# ProPrj_ESP32S3R8N8_CAN_Board_2026-01-26.net
KiCad netlist of a schematic drawn in EasyEDA Pro
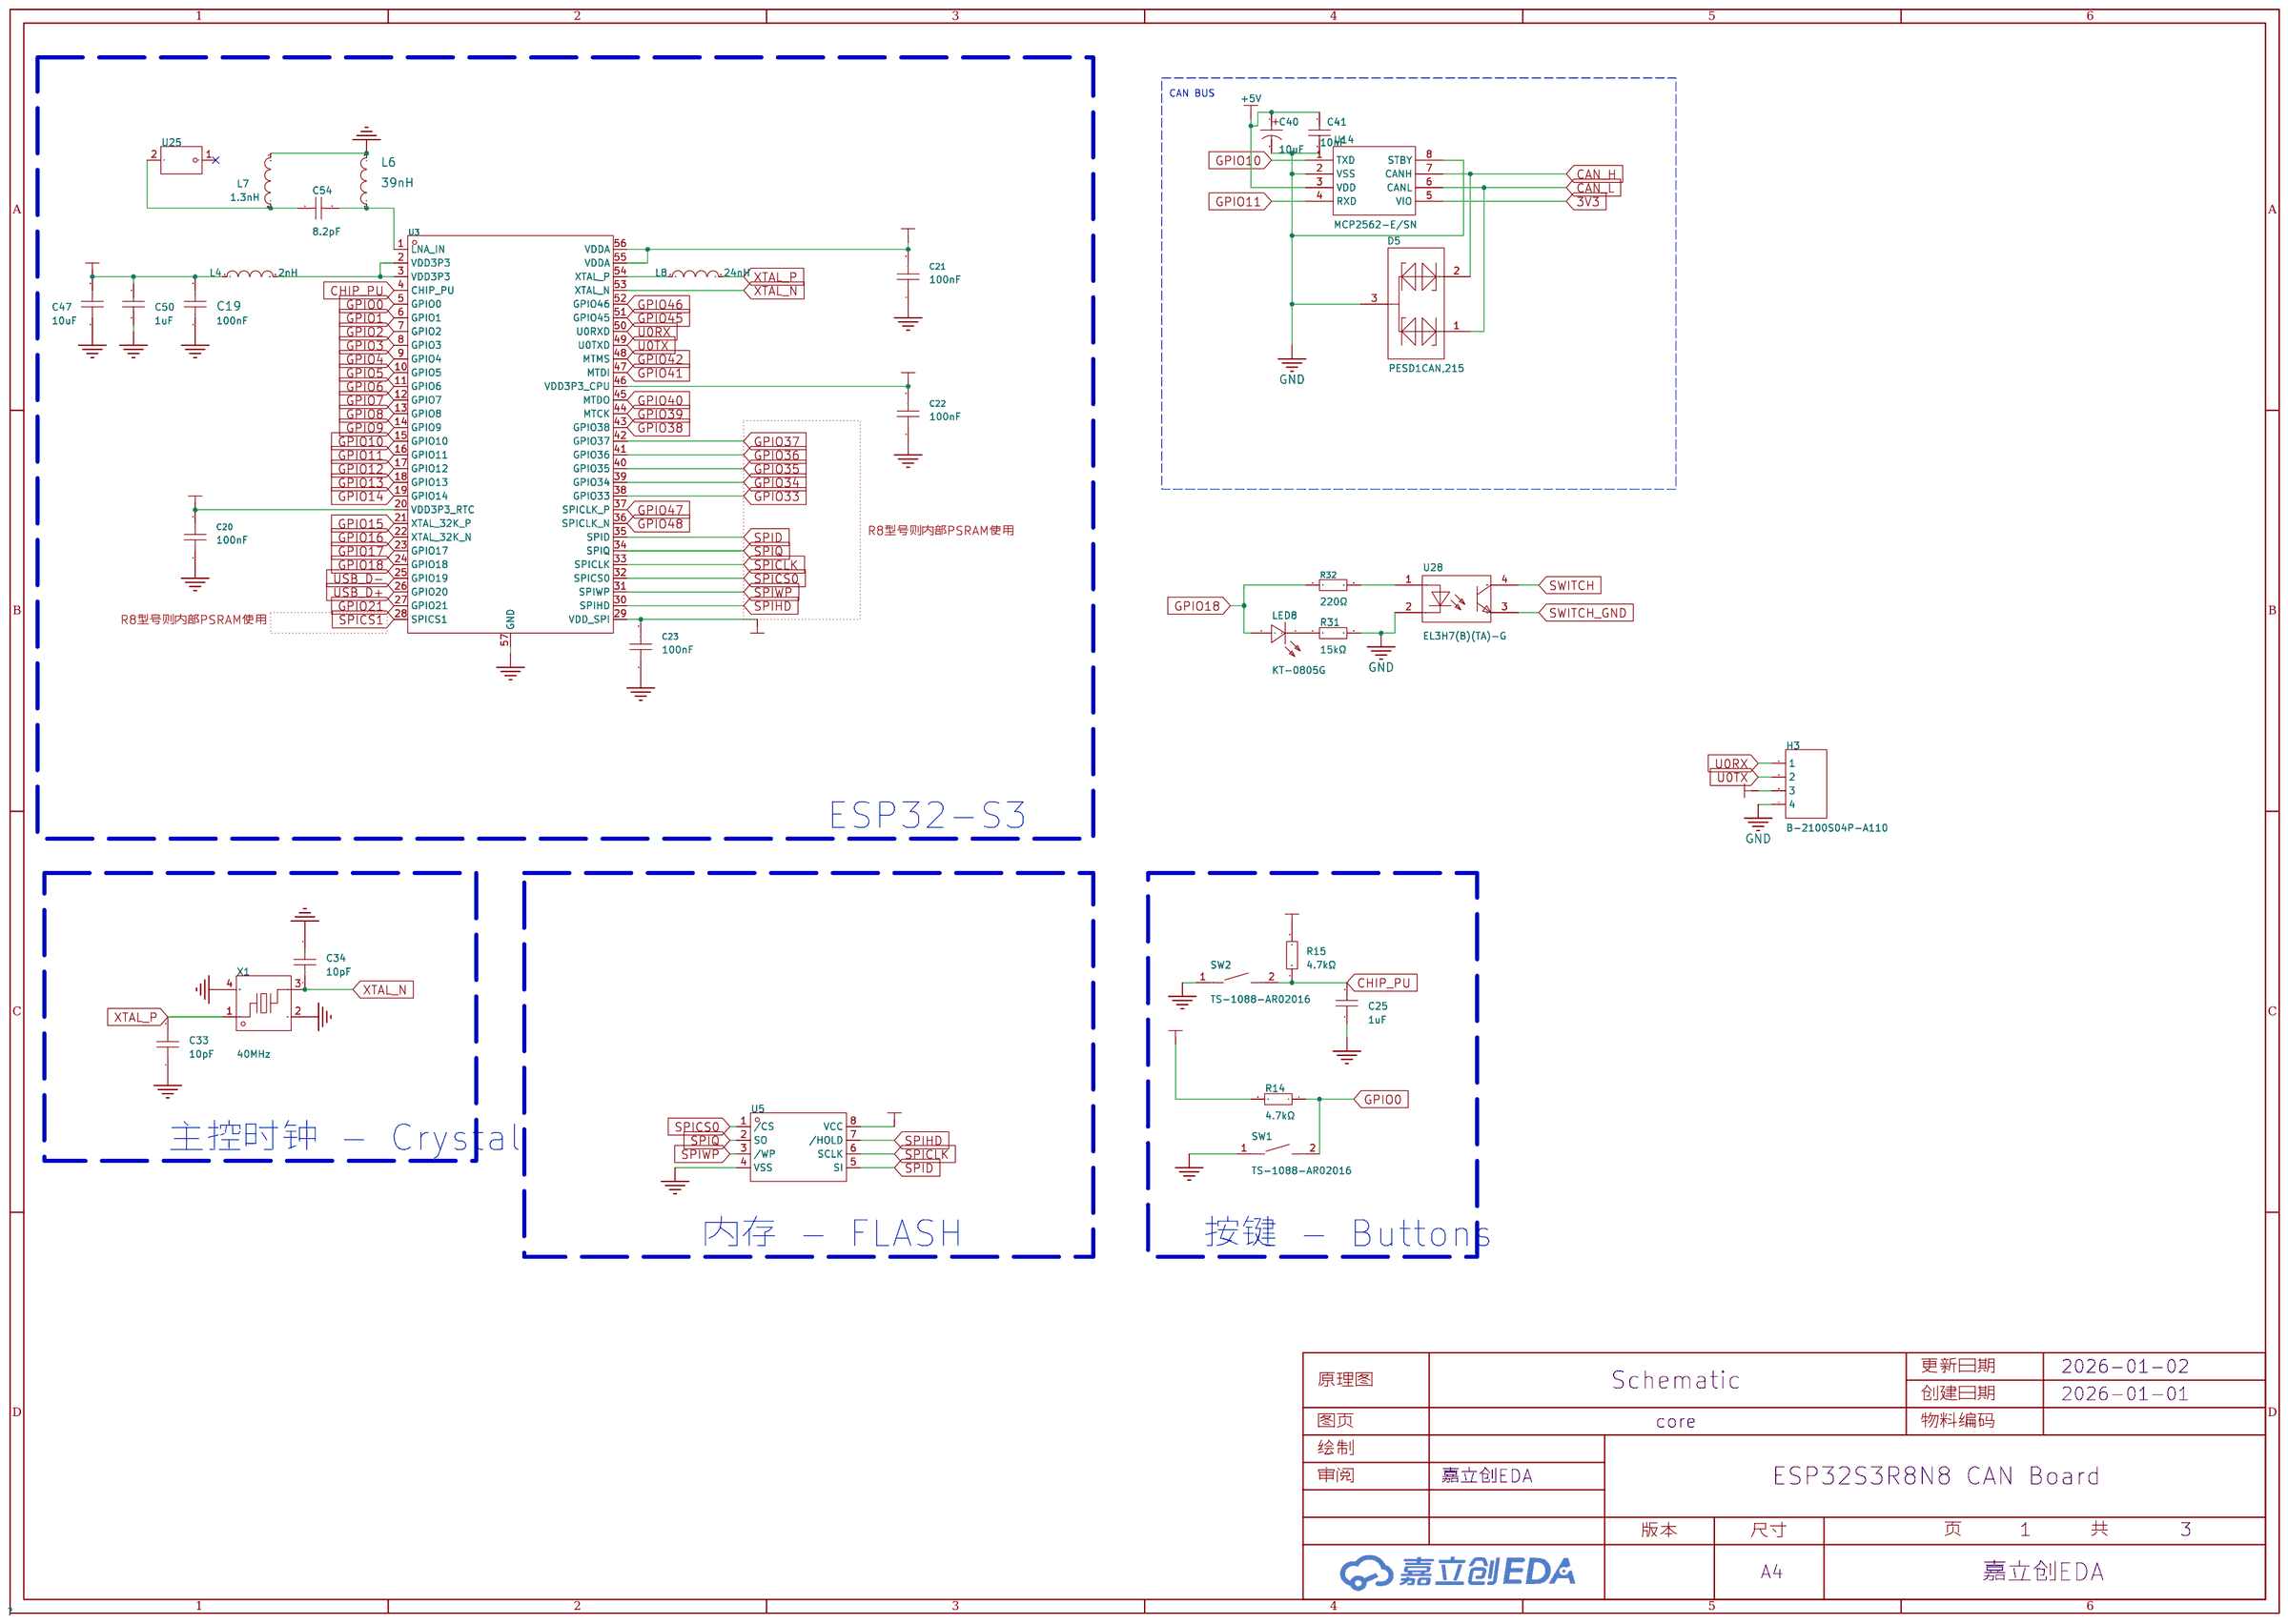
[diagram p0: core]
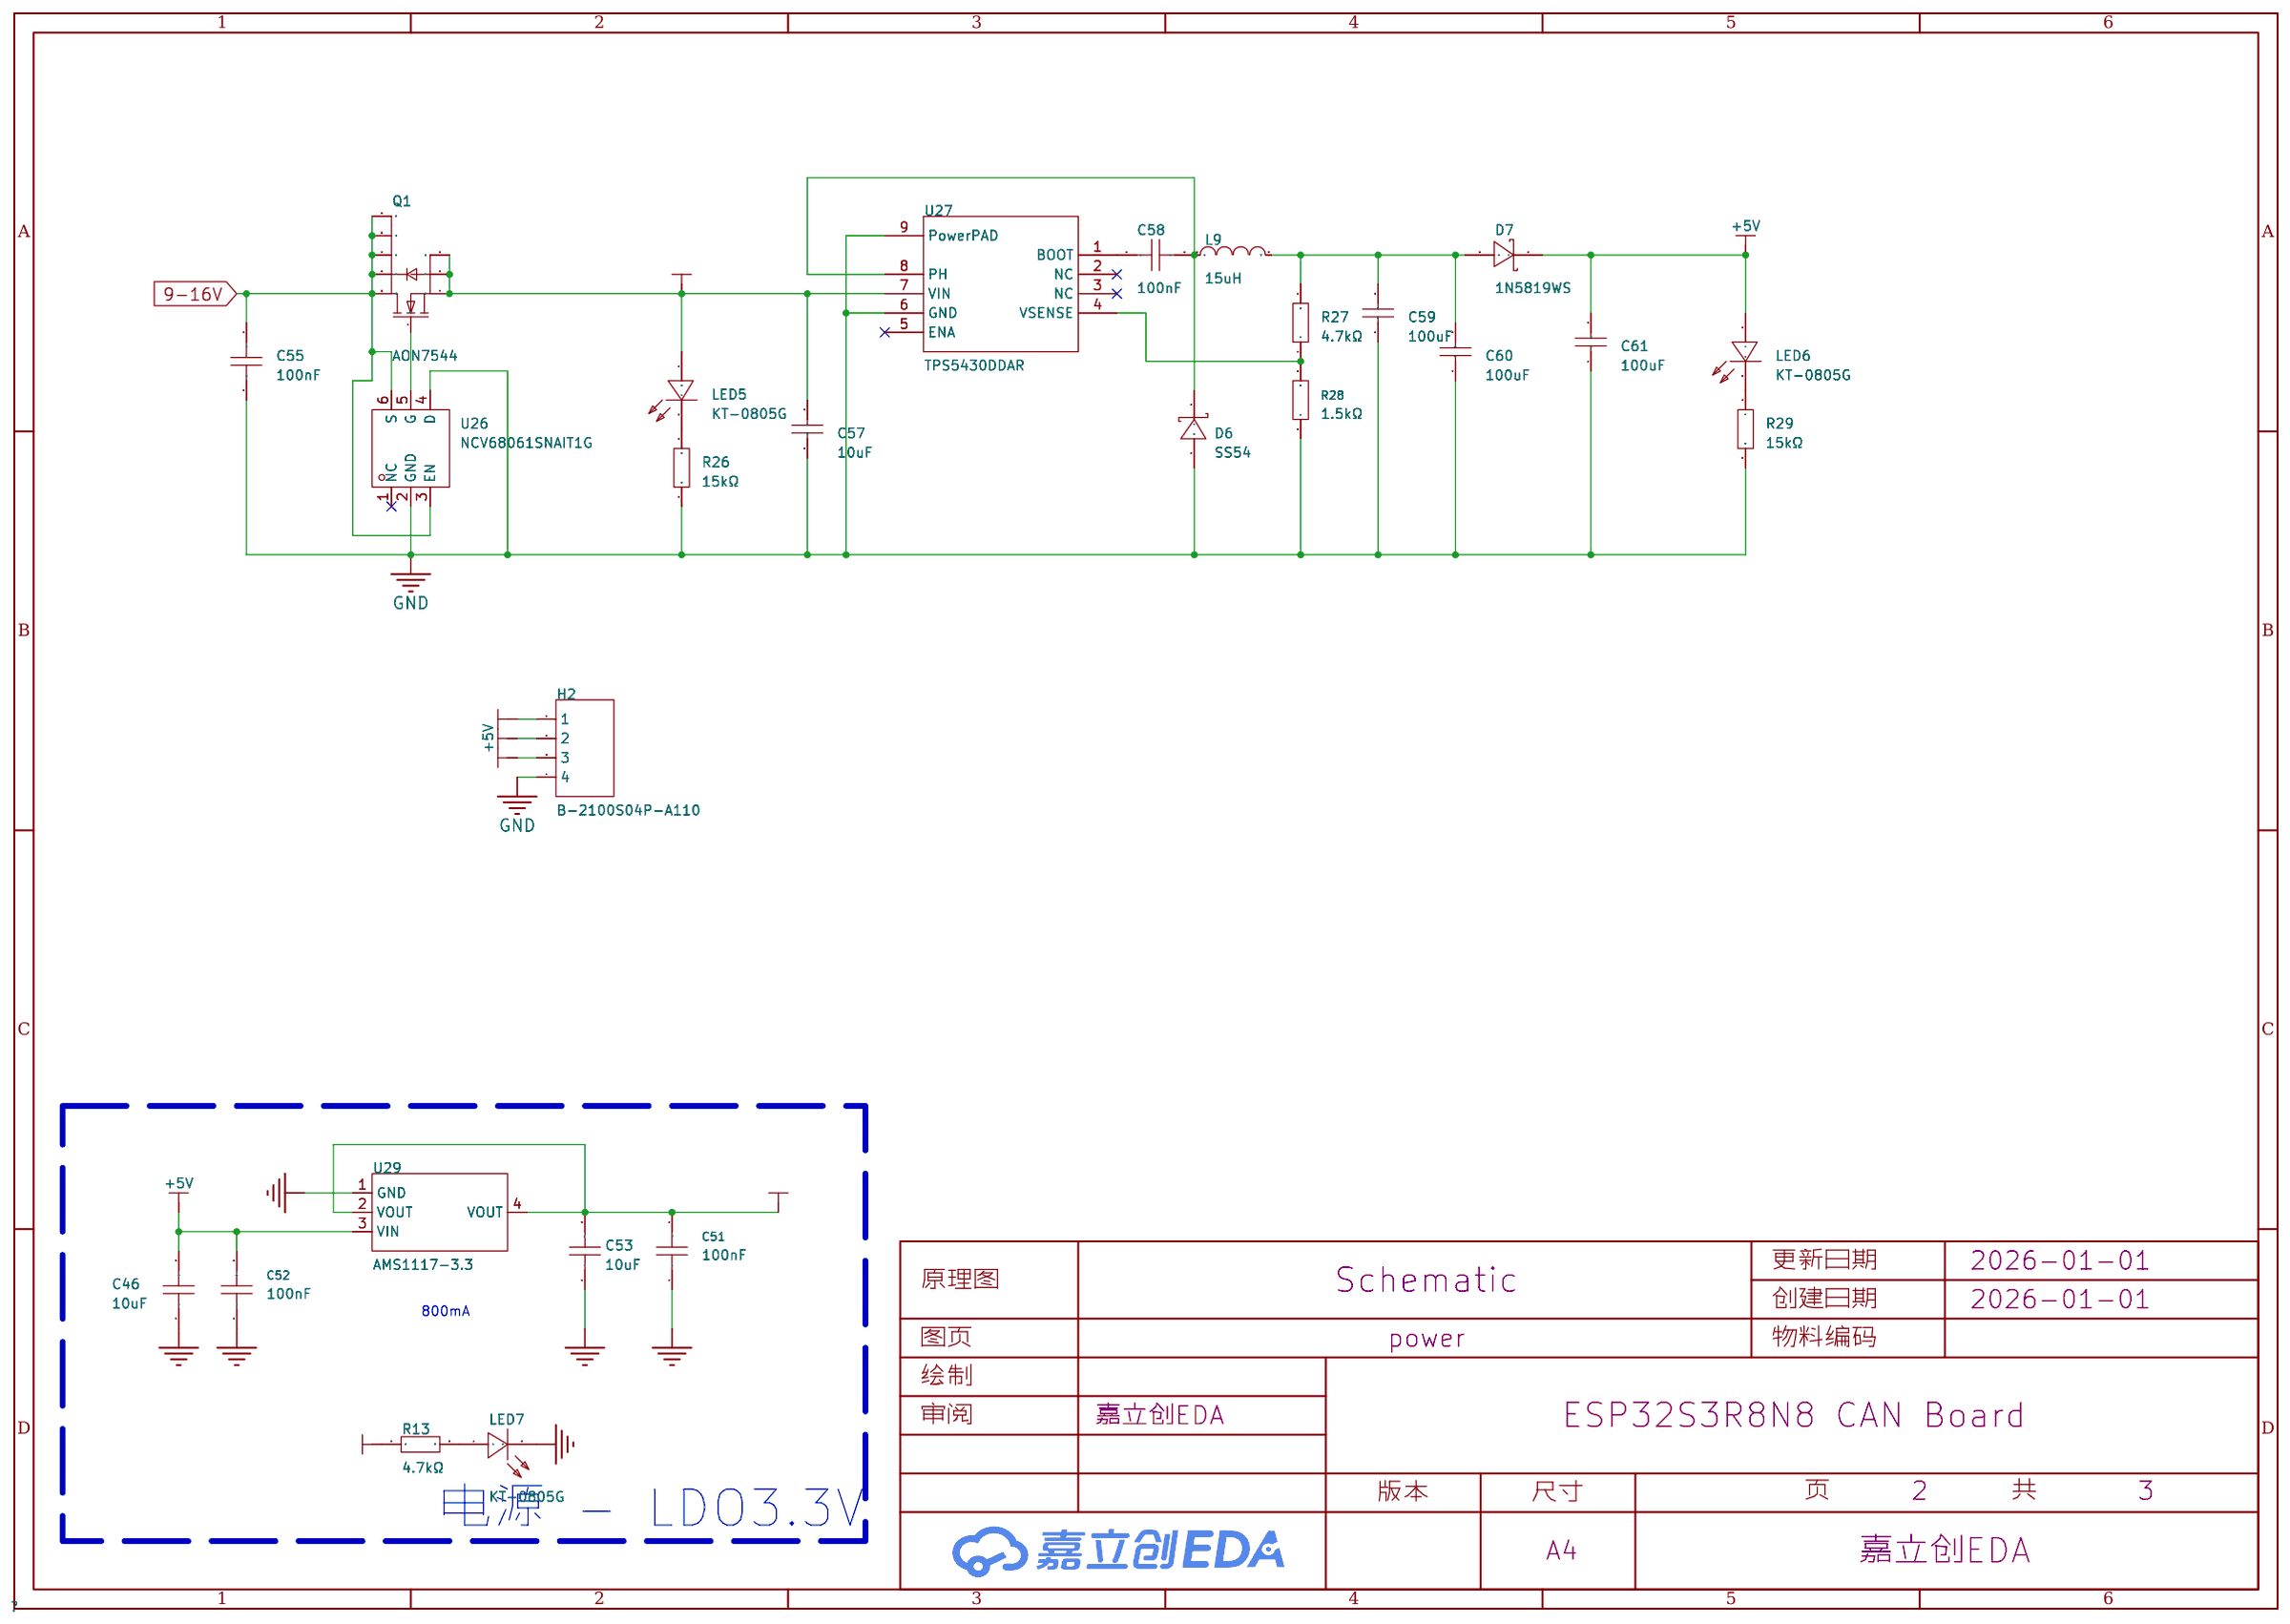
[diagram p1: power]
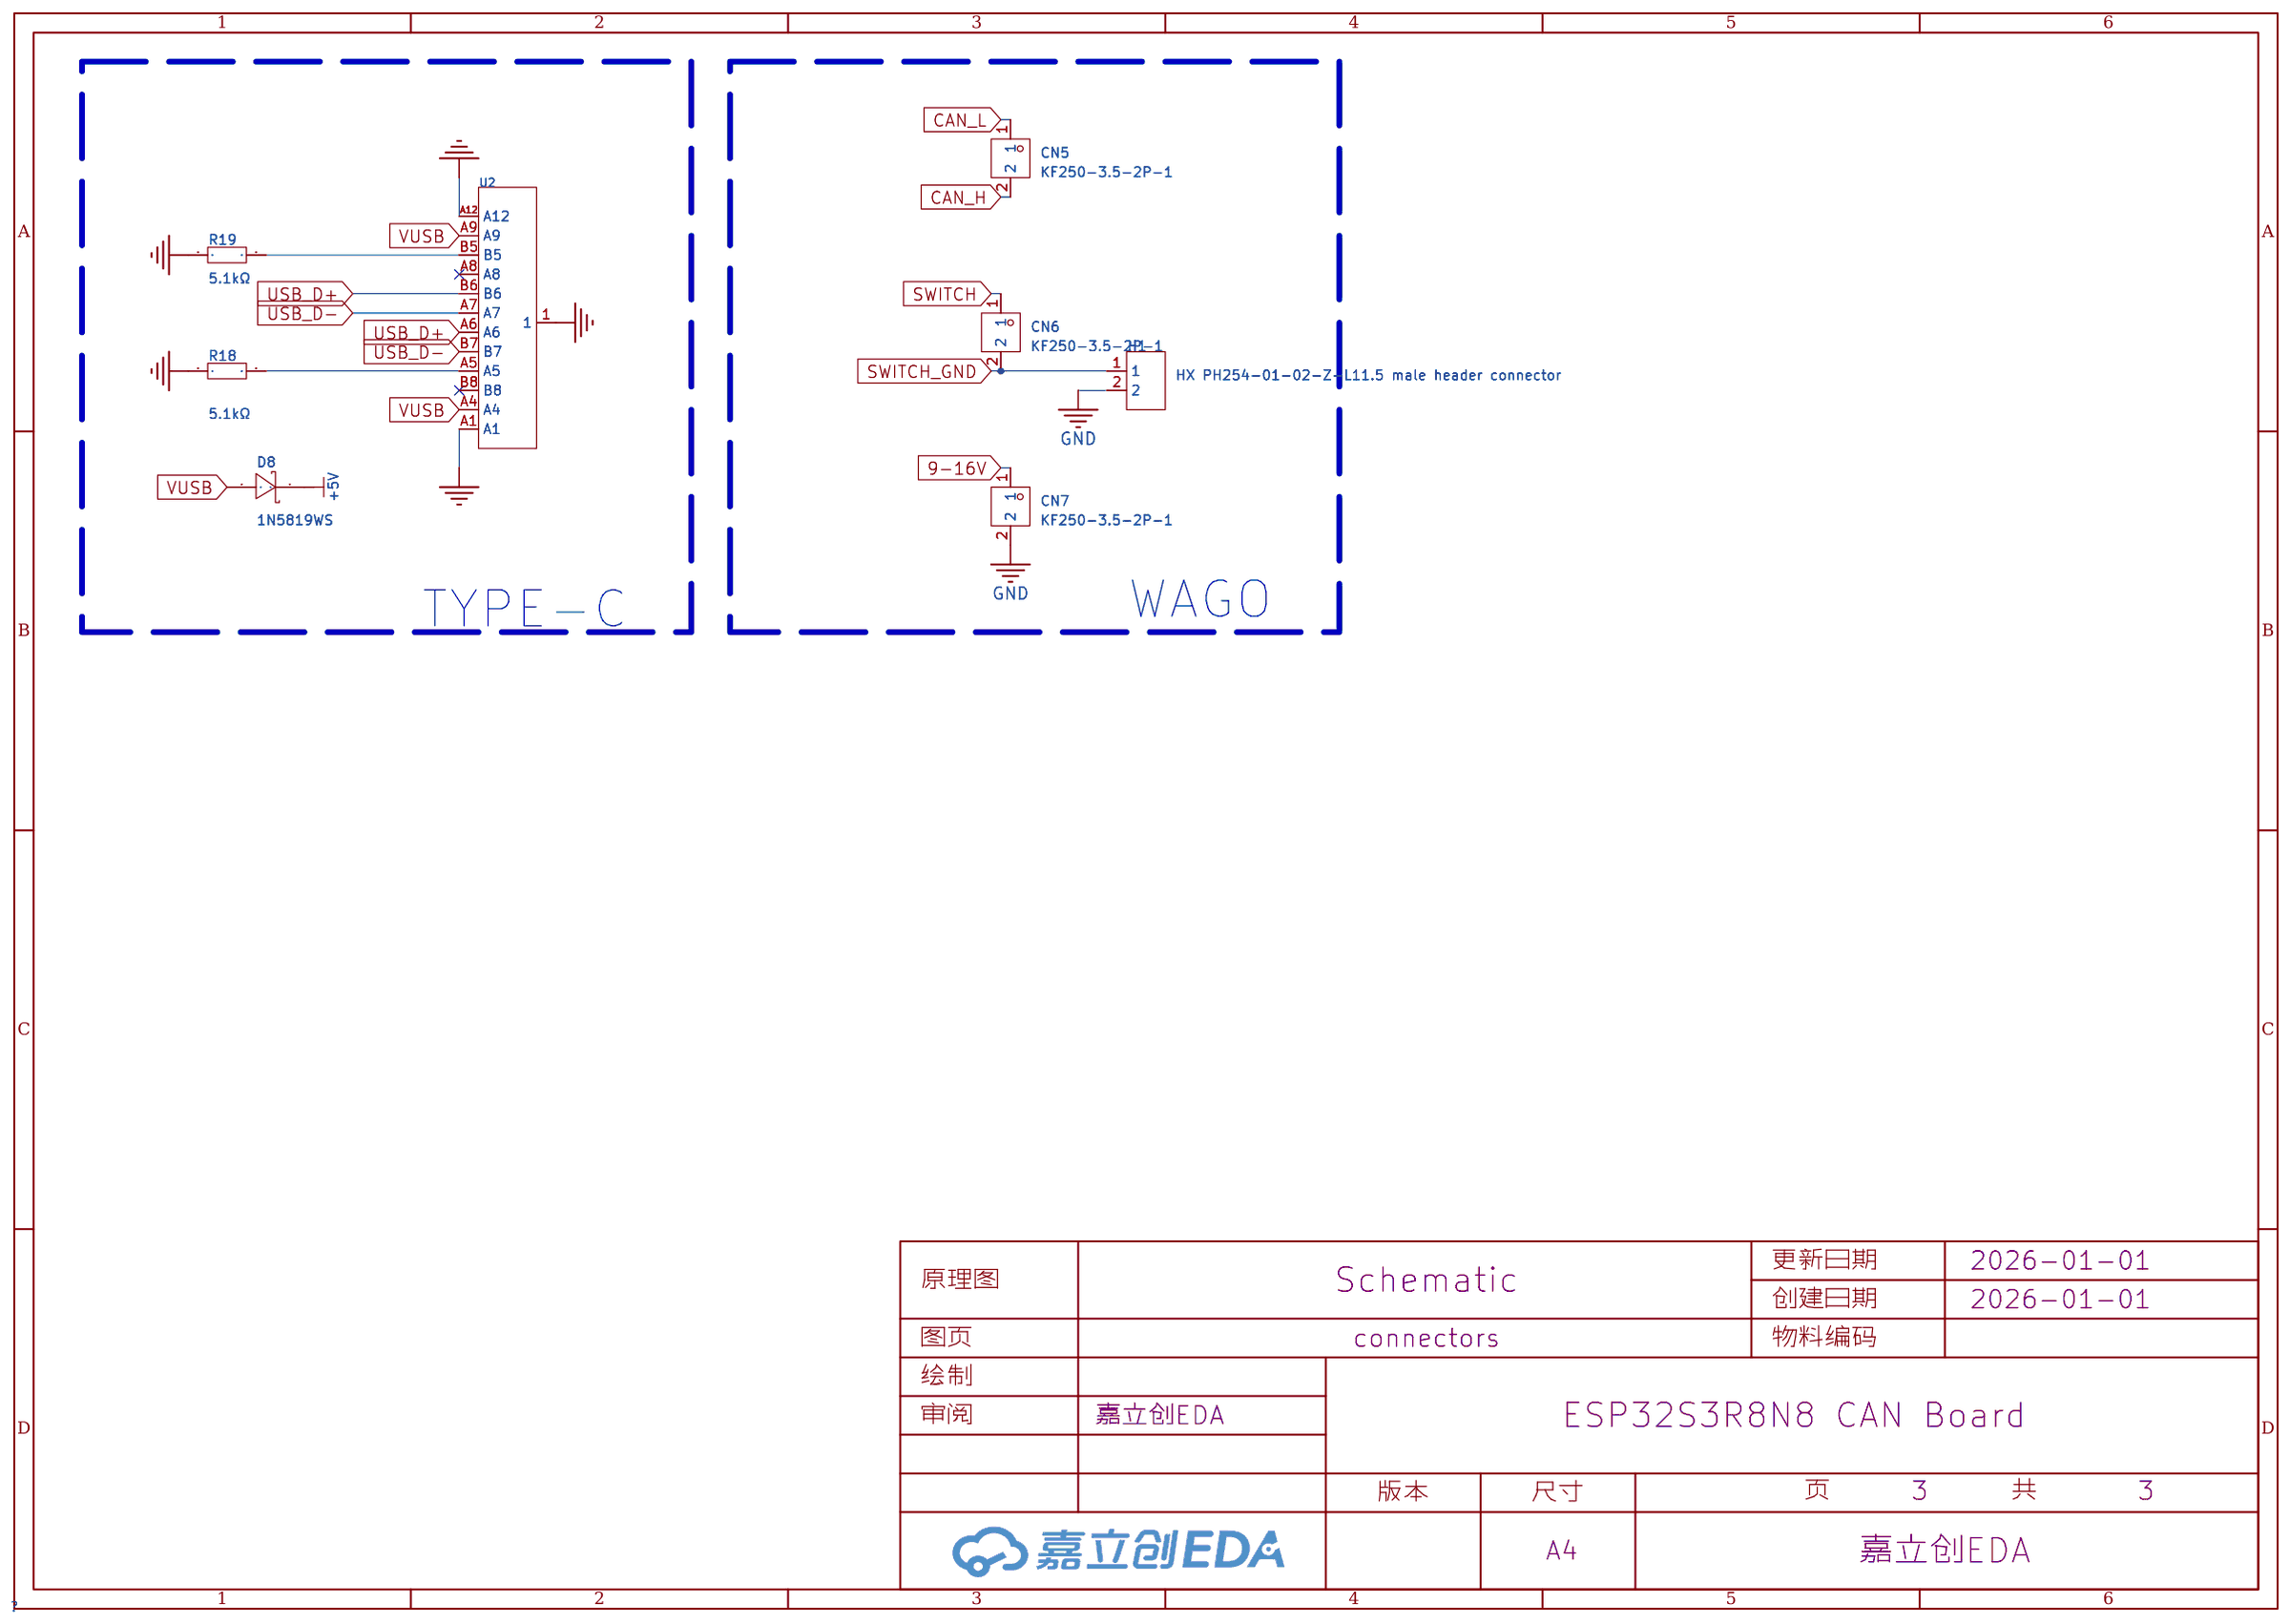
[diagram p2: connectors]

(export (version "E")
  (design (tool "Eeschema 10.0.6"))
  (components
    (comp (ref "C19")
      (value "100nF")
      (footprint "easyedapro:C0402")
      (description "容值:100nF;精度:±10%;额定电压:50V;材质(温度系数):X7R;")
      (fields
        (field (name "Manufacturer Part") "GRM155R71H104KE14D")
        (field (name "Manufacturer") "muRata(村田)")
      )
      (libsource (lib "easyedapro") (part "GRM155R71H104KE14D"))
    )
    (comp (ref "C20")
      (value "100nF")
      (footprint "easyedapro:C0402")
      (description "容值:100nF;精度:±10%;额定电压:50V;材质(温度系数):X7R;")
      (fields
        (field (name "Manufacturer Part") "GRM155R71H104KE14D")
        (field (name "Manufacturer") "muRata(村田)")
      )
      (libsource (lib "easyedapro") (part "GRM155R71H104KE14D"))
    )
    (comp (ref "C21")
      (value "100nF")
      (footprint "easyedapro:C0402")
      (description "容值:100nF;精度:±10%;额定电压:50V;材质(温度系数):X7R;")
      (fields
        (field (name "Manufacturer Part") "GRM155R71H104KE14D")
        (field (name "Manufacturer") "muRata(村田)")
      )
      (libsource (lib "easyedapro") (part "GRM155R71H104KE14D"))
    )
    (comp (ref "C22")
      (value "100nF")
      (footprint "easyedapro:C0402")
      (description "容值:100nF;精度:±10%;额定电压:50V;材质(温度系数):X7R;")
      (fields
        (field (name "Manufacturer Part") "GRM155R71H104KE14D")
        (field (name "Manufacturer") "muRata(村田)")
      )
      (libsource (lib "easyedapro") (part "GRM155R71H104KE14D"))
    )
    (comp (ref "C23")
      (value "100nF")
      (footprint "easyedapro:C0402")
      (description "容值:100nF;精度:±10%;额定电压:50V;材质(温度系数):X7R;")
      (fields
        (field (name "Manufacturer Part") "GRM155R71H104KE14D")
        (field (name "Manufacturer") "muRata(村田)")
      )
      (libsource (lib "easyedapro") (part "GRM155R71H104KE14D"))
    )
    (comp (ref "C25")
      (value "1uF")
      (footprint "easyedapro:C0402")
      (description "容值:1uF;精度:±10%;额定电压:10V;材质(温度系数):X5R;")
      (fields
        (field (name "Manufacturer Part") "CL05A105KP5NNNC")
        (field (name "Manufacturer") "SAMSUNG(三星)")
      )
      (libsource (lib "easyedapro") (part "CL05A105KP5NNNC"))
    )
    (comp (ref "C33")
      (value "10pF")
      (footprint "easyedapro:C0402")
      (description "容值:10pF;精度:±5%;额定电压:50V;材质(温度系数):C0G;")
      (fields
        (field (name "Manufacturer Part") "CL05C100JB5NNNC")
        (field (name "Manufacturer") "SAMSUNG(三星)")
      )
      (libsource (lib "easyedapro") (part "CL05C100JB5NNNC"))
    )
    (comp (ref "C34")
      (value "10pF")
      (footprint "easyedapro:C0402")
      (description "容值:10pF;精度:±5%;额定电压:50V;材质(温度系数):C0G;")
      (fields
        (field (name "Manufacturer Part") "CL05C100JB5NNNC")
        (field (name "Manufacturer") "SAMSUNG(三星)")
      )
      (libsource (lib "easyedapro") (part "CL05C100JB5NNNC"))
    )
    (comp (ref "C40")
      (value "10uF")
      (description "Capacitance:10uF Tolerance:±10% Tolerance:±10% Voltage Rating:50V Temperature Coefficient:X5R")
      (fields
        (field (name "Manufacturer Part") "CL31A106KBHNNNE")
        (field (name "Manufacturer") "SAMSUNG(三星)")
      )
      (libsource (lib "easyedapro") (part "CS1E100M-CRC54"))
    )
    (comp (ref "C41")
      (value "10nF")
      (footprint "easyedapro:C0402")
      (fields (field (name "Manufacturer Part") "CGA2B2X7R1E103KT0Y0F") (field (name "Manufacturer") "TDK"))
      (libsource (lib "easyedapro") (part "CGA2B2X7R1E103KT0Y0F"))
    )
    (comp (ref "C47")
      (value "10uF")
      (footprint "easyedapro:C0402")
      (description "Capacitance:10uF Tolerance:±10% Tolerance:±10% Voltage Rating:50V Temperature Coefficient:X5R")
      (fields
        (field (name "Manufacturer Part") "CL31A106KBHNNNE")
        (field (name "Manufacturer") "SAMSUNG(三星)")
      )
      (libsource (lib "easyedapro") (part "GRM155R61A106ME44D"))
    )
    (comp (ref "C50")
      (value "1uF")
      (footprint "easyedapro:C0402")
      (description "容值:1uF;精度:±10%;额定电压:10V;材质(温度系数):X5R;")
      (fields
        (field (name "Manufacturer Part") "CL05A105KP5NNNC")
        (field (name "Manufacturer") "SAMSUNG(三星)")
      )
      (libsource (lib "easyedapro") (part "CL05A105KP5NNNC"))
    )
    (comp (ref "C54")
      (value "8.2pF")
      (footprint "easyedapro:C0402")
      (description "容值:8.2pF;额定电压:50V;材质(温度系数):C0G;")
      (fields (field (name "Manufacturer Part") "0402CG8R2C500NT") (field (name "Manufacturer") "FH(风华)"))
      (libsource (lib "easyedapro") (part "0402CG8R2C500NT"))
    )
    (comp (ref "D5")
      (value "PESD1CAN,215")
      (footprint "easyedapro:SOT-23_L2.9-W1.3-P1.90-LS2.4-BR")
      (fields (field (name "Manufacturer") "Nexperia(安世)"))
      (libsource (lib "easyedapro") (part "PESD1CAN,215"))
    )
    (comp (ref "H3")
      (value "B-2100S04P-A110")
      (footprint "easyedapro:HDR-TH_4P-P2.54-V-M")
      (fields (field (name "Manufacturer") "Ckmtw(灿科盟)"))
      (libsource (lib "easyedapro") (part "Header-Male-2.54_1x4"))
    )
    (comp (ref "L4")
      (value "2nH")
      (footprint "easyedapro:L0402")
      (description "电感值:2nH;精度:-;额定电流:900mA;饱和电流(Isat):-;直流电阻(DCR):70mΩ;")
      (fields (field (name "Manufacturer Part") "MLG1005S2N0BT000") (field (name "Manufacturer") "TDK"))
      (libsource (lib "easyedapro") (part "MLG1005S2N0BT000"))
    )
    (comp (ref "L6")
      (value "39nH")
      (footprint "easyedapro:L0402")
      (description "电感值:39nH;额定电流:200mA;直流电阻(DCR):1Ω;精度:±5%;")
      (fields
        (field (name "Manufacturer Part") "SDCL1005C39NJTDF")
        (field (name "Manufacturer") "Sunlord(顺络)")
      )
      (libsource (lib "easyedapro") (part "SDCL1005C39NJTDF"))
    )
    (comp (ref "L7")
      (value "1.3nH")
      (footprint "easyedapro:L0402-RD")
      (description "电感值:1.3nH;精度:-;额定电流:400mA;直流电阻(DCR):100mΩ;饱和电流(Isat):-;")
      (fields
        (field (name "Manufacturer Part") "SDCL1005C1N3STDF")
        (field (name "Manufacturer") "Sunlord(顺络)")
      )
      (libsource (lib "easyedapro") (part "SDCL1005C1N3STDF"))
    )
    (comp (ref "L8")
      (value "24nH")
      (footprint "easyedapro:L0402-RD")
      (description "电感值:24nH;精度:±5%;额定电流:-;饱和电流(Isat):-;直流电阻(DCR):-;")
      (fields
        (field (name "Manufacturer Part") "SDCL1005C24NJTDF")
        (field (name "Manufacturer") "Sunlord(顺络)")
      )
      (libsource (lib "easyedapro") (part "SDCL1005C24NJTDF"))
    )
    (comp (ref "LED8")
      (value "KT-0805G")
      (footprint "easyedapro:LED0805-R-RD")
      (fields (field (name "Manufacturer") "KENTO"))
      (libsource (lib "easyedapro") (part "0805G (Green)"))
    )
    (comp (ref "R14")
      (value "4.7kΩ")
      (footprint "easyedapro:R0402")
      (fields
        (field (name "Manufacturer Part") "0402WGF4701TCE")
        (field (name "Manufacturer") "UNI-ROYAL(厚声)")
      )
      (libsource (lib "easyedapro") (part "0402WGJ0472TCE"))
    )
    (comp (ref "R15")
      (value "4.7kΩ")
      (footprint "easyedapro:R0402")
      (fields
        (field (name "Manufacturer Part") "0402WGF4701TCE")
        (field (name "Manufacturer") "UNI-ROYAL(厚声)")
      )
      (libsource (lib "easyedapro") (part "0402WGJ0472TCE"))
    )
    (comp (ref "R31")
      (value "15kΩ")
      (footprint "easyedapro:R0402")
      (description "电阻类型:厚膜电阻;阻值:15kΩ;精度:±1%;功率:62.5mW;")
      (fields
        (field (name "Manufacturer Part") "0402WGF1502TCE")
        (field (name "Manufacturer") "UNI-ROYAL(厚声)")
      )
      (libsource (lib "easyedapro") (part "0402WGF1502TCE"))
    )
    (comp (ref "R32")
      (value "220Ω")
      (footprint "easyedapro:R0402")
      (fields
        (field (name "Manufacturer Part") "0402WGF2200TCE")
        (field (name "Manufacturer") "UNI-ROYAL(厚声)")
      )
      (libsource (lib "easyedapro") (part "0402WGF2200TCE"))
    )
    (comp (ref "SW1")
      (value "TS-1088-AR02016")
      (footprint "easyedapro:SW-SMD_L3.9-W3.0-P4.45")
      (fields (field (name "Manufacturer") "XUNPU(讯普)"))
      (libsource (lib "easyedapro") (part "TS-1088-AR02016"))
    )
    (comp (ref "SW2")
      (value "TS-1088-AR02016")
      (footprint "easyedapro:SW-SMD_L3.9-W3.0-P4.45")
      (fields (field (name "Manufacturer") "XUNPU(讯普)"))
      (libsource (lib "easyedapro") (part "TS-1088-AR02016"))
    )
    (comp (ref "U3")
      (value "ESP32-S3(R8)")
      (footprint "easyedapro:QFN-56_L7.0-W7.0-P0.40-TL-EP4.0")
      (description "应用领域:蓝牙,WiFi;频率范围:2.412GHz~2.484GHz;数据速率:150Mbps;灵敏度:-98.4dBm;接口:I2C,I2S,SPI,UART,USB;")
      (fields (field (name "Manufacturer") "ESPRESSIF(乐鑫)"))
      (libsource (lib "easyedapro") (part "ESP32-S3(R8)"))
    )
    (comp (ref "U5")
      (value "BY25Q64ASSIG(T)")
      (footprint "easyedapro:SOIC-8_L5.3-W5.3-P1.27-LS8.0-BL")
      (fields (field (name "Manufacturer") "BOYAMICRO(博雅)"))
      (libsource (lib "easyedapro") (part "BY25Q64ASSIG(T)"))
    )
    (comp (ref "U14")
      (value "MCP2562-E/SN")
      (footprint "easyedapro:SOIC-8_L5.0-W4.0-P1.27-LS6.0-BL")
      (description "Type:Transceiver Supply Voltage:4.5V~5.5V Supply Voltage:4.5V~5.5V")
      (fields (field (name "Manufacturer") "MICROCHIP(美国微芯)"))
      (libsource (lib "easyedapro") (part "MCP2562-E/SN"))
    )
    (comp (ref "U25")
      (value "RFANT5220110A0T")
      (footprint "easyedapro:FILTER-SMD_L5.2-W2.0-L")
      (description "2.4 GHz 陶瓷天线")
      (fields (field (name "Manufacturer") "Walsin(华新科)"))
      (libsource (lib "easyedapro") (part "RFANT5220110A0T"))
    )
    (comp (ref "U28")
      (value "EL3H7(B)(TA)-G")
      (footprint "easyedapro:SSOP-4_L4.4-W2.7-P1.27-LS7.0-TL")
      (fields (field (name "Manufacturer") "EVERLIGHT(亿光)"))
      (libsource (lib "easyedapro") (part "EL3H7(B)(TA)-G_C5213653"))
    )
    (comp (ref "X1")
      (value "40MHz")
      (footprint "easyedapro:CRYSTAL-SMD_4P-L2.5-W2.0-BL")
      (description "频率:40MHz;频率公差:±10ppm;负载电容:10pF;")
      (fields (field (name "Manufacturer Part") "S2240000101050JY") (field (name "Manufacturer") "JGHC(晶光华)"))
      (libsource (lib "easyedapro") (part "S2240000101050JY"))
    )
    (comp (ref "C46")
      (value "10uF")
      (footprint "easyedapro:C0402")
      (description "Capacitance:10uF Tolerance:±10% Tolerance:±10% Voltage Rating:50V Temperature Coefficient:X5R")
      (fields
        (field (name "Manufacturer Part") "CL31A106KBHNNNE")
        (field (name "Manufacturer") "SAMSUNG(三星)")
      )
      (libsource (lib "easyedapro") (part "GRM155R61A106ME44D"))
    )
    (comp (ref "C51")
      (value "100nF")
      (footprint "easyedapro:C0402")
      (description "Capacitance:100nF Tolerance:±10% Tolerance:±10% Voltage Rating:50V Temperature Coefficient:X7R")
      (fields
        (field (name "Manufacturer Part") "CC0603KRX7R9BB104")
        (field (name "Manufacturer") "YAGEO(国巨)")
      )
      (libsource (lib "easyedapro") (part "GRM155R71H104KE14D"))
    )
    (comp (ref "C52")
      (value "100nF")
      (footprint "easyedapro:C0402")
      (description "Capacitance:100nF Tolerance:±10% Tolerance:±10% Voltage Rating:50V Temperature Coefficient:X7R")
      (fields
        (field (name "Manufacturer Part") "CC0603KRX7R9BB104")
        (field (name "Manufacturer") "YAGEO(国巨)")
      )
      (libsource (lib "easyedapro") (part "GRM155R71H104KE14D"))
    )
    (comp (ref "C53")
      (value "10uF")
      (footprint "easyedapro:C0402")
      (description "Capacitance:10uF Tolerance:±10% Tolerance:±10% Voltage Rating:50V Temperature Coefficient:X5R")
      (fields
        (field (name "Manufacturer Part") "CL31A106KBHNNNE")
        (field (name "Manufacturer") "SAMSUNG(三星)")
      )
      (libsource (lib "easyedapro") (part "GRM155R61A106ME44D"))
    )
    (comp (ref "C55")
      (value "100nF")
      (footprint "easyedapro:C0603")
      (description "Capacitance:100nF Tolerance:±10% Tolerance:±10% Voltage Rating:50V Temperature Coefficient:X7R")
      (fields
        (field (name "Manufacturer Part") "CC0603KRX7R9BB104")
        (field (name "Manufacturer") "YAGEO(国巨)")
      )
      (libsource (lib "easyedapro") (part "CC0603KRX7R9BB104"))
    )
    (comp (ref "C57")
      (value "10uF")
      (footprint "easyedapro:C1206")
      (description "Capacitance:10uF Tolerance:±10% Tolerance:±10% Voltage Rating:50V Temperature Coefficient:X5R")
      (fields
        (field (name "Manufacturer Part") "CL31A106KBHNNNE")
        (field (name "Manufacturer") "SAMSUNG(三星)")
      )
      (libsource (lib "easyedapro") (part "CL31A106KBHNNNE"))
    )
    (comp (ref "C58")
      (value "100nF")
      (footprint "easyedapro:C0603")
      (description "Capacitance:100nF Tolerance:±10% Tolerance:±10% Voltage Rating:50V Temperature Coefficient:X7R")
      (fields
        (field (name "Manufacturer Part") "CC0603KRX7R9BB104")
        (field (name "Manufacturer") "YAGEO(国巨)")
      )
      (libsource (lib "easyedapro") (part "CC0603KRX7R9BB104"))
    )
    (comp (ref "C59")
      (value "100uF")
      (footprint "easyedapro:C1206")
      (description "Capacitance:100uF Tolerance:±20% Tolerance:±20% Voltage Rating:6.3V Temperature Coefficient:X5R")
      (fields
        (field (name "Manufacturer Part") "CL31A107MQHNNNE")
        (field (name "Manufacturer") "SAMSUNG(三星)")
      )
      (libsource (lib "easyedapro") (part "CL31A107MQHNNNE"))
    )
    (comp (ref "C60")
      (value "100uF")
      (footprint "easyedapro:C1206")
      (description "Capacitance:100uF Tolerance:±20% Tolerance:±20% Voltage Rating:6.3V Temperature Coefficient:X5R")
      (fields
        (field (name "Manufacturer Part") "CL31A107MQHNNNE")
        (field (name "Manufacturer") "SAMSUNG(三星)")
      )
      (libsource (lib "easyedapro") (part "CL31A107MQHNNNE"))
    )
    (comp (ref "C61")
      (value "100uF")
      (footprint "easyedapro:C1206")
      (description "Capacitance:100uF Tolerance:±20% Tolerance:±20% Voltage Rating:6.3V Temperature Coefficient:X5R")
      (fields
        (field (name "Manufacturer Part") "CL31A107MQHNNNE")
        (field (name "Manufacturer") "SAMSUNG(三星)")
      )
      (libsource (lib "easyedapro") (part "CL31A107MQHNNNE"))
    )
    (comp (ref "D6")
      (value "SS54")
      (footprint "easyedapro:SMA_L4.4-W2.8-LS5.4-R-RD")
      (fields (field (name "Manufacturer") "MDD(辰达半导体)"))
      (libsource (lib "easyedapro") (part "SS54_C22452"))
    )
    (comp (ref "D7")
      (value "1N5819WS")
      (footprint "easyedapro:SOD-323_L1.8-W1.3-LS2.5-RD")
      (fields (field (name "Manufacturer") "Hottech(合科泰)"))
      (libsource (lib "easyedapro") (part "1N5819WS"))
    )
    (comp (ref "H2")
      (value "B-2100S04P-A110")
      (footprint "easyedapro:HDR-TH_4P-P2.54-V-M")
      (fields (field (name "Manufacturer") "Ckmtw(灿科盟)"))
      (libsource (lib "easyedapro") (part "Header-Male-2.54_1x4"))
    )
    (comp (ref "L9")
      (value "15uH")
      (footprint "easyedapro:IND-SMD_L7.0-W6.6_FXL0630")
      (fields (field (name "Manufacturer Part") "FXL0630-150-M") (field (name "Manufacturer") "cjiang(长江微电)"))
      (libsource (lib "easyedapro") (part "FXL0630-150-M"))
    )
    (comp (ref "LED5")
      (value "KT-0805G")
      (footprint "easyedapro:LED0805-R-RD")
      (fields (field (name "Manufacturer") "KENTO"))
      (libsource (lib "easyedapro") (part "0805G (Green)"))
    )
    (comp (ref "LED6")
      (value "KT-0805G")
      (footprint "easyedapro:LED0805-R-RD")
      (fields (field (name "Manufacturer") "KENTO"))
      (libsource (lib "easyedapro") (part "0805G (Green)"))
    )
    (comp (ref "LED7")
      (value "KT-0805G")
      (footprint "easyedapro:LED0805-R-RD")
      (fields (field (name "Manufacturer") "KENTO"))
      (libsource (lib "easyedapro") (part "0805G (Green)"))
    )
    (comp (ref "Q1")
      (value "AON7544")
      (footprint "easyedapro:DFN-8_L3.2-W3.1-P0.65-LS3.4-BL")
      (fields (field (name "Manufacturer") "HXY MOSFET(华轩阳电子)"))
      (libsource (lib "easyedapro") (part "AON7544_C5261066"))
    )
    (comp (ref "R13")
      (value "4.7kΩ")
      (footprint "easyedapro:R0402")
      (fields
        (field (name "Manufacturer Part") "0402WGF4701TCE")
        (field (name "Manufacturer") "UNI-ROYAL(厚声)")
      )
      (libsource (lib "easyedapro") (part "0402WGJ0472TCE"))
    )
    (comp (ref "R26")
      (value "15kΩ")
      (footprint "easyedapro:R0402")
      (description "电阻类型:厚膜电阻;阻值:15kΩ;精度:±1%;功率:62.5mW;")
      (fields
        (field (name "Manufacturer Part") "0402WGF1502TCE")
        (field (name "Manufacturer") "UNI-ROYAL(厚声)")
      )
      (libsource (lib "easyedapro") (part "0402WGF1502TCE"))
    )
    (comp (ref "R27")
      (value "4.7kΩ")
      (footprint "easyedapro:R0402")
      (fields
        (field (name "Manufacturer Part") "0402WGF4701TCE")
        (field (name "Manufacturer") "UNI-ROYAL(厚声)")
      )
      (libsource (lib "easyedapro") (part "0402WGJ0472TCE"))
    )
    (comp (ref "R28")
      (value "1.5kΩ")
      (footprint "easyedapro:R0402")
      (fields
        (field (name "Manufacturer Part") "0402WGF1501TCE")
        (field (name "Manufacturer") "UNI-ROYAL(厚声)")
      )
      (libsource (lib "easyedapro") (part "0402WGF1501TCE"))
    )
    (comp (ref "R29")
      (value "15kΩ")
      (footprint "easyedapro:R0402")
      (description "电阻类型:厚膜电阻;阻值:15kΩ;精度:±1%;功率:62.5mW;")
      (fields
        (field (name "Manufacturer Part") "0402WGF1502TCE")
        (field (name "Manufacturer") "UNI-ROYAL(厚声)")
      )
      (libsource (lib "easyedapro") (part "0402WGF1502TCE"))
    )
    (comp (ref "U26")
      (value "NCV68061SNAIT1G")
      (footprint "easyedapro:TSOP-6_L3.0-W1.5-P0.95-BL")
      (fields (field (name "Manufacturer") "onsemi(安森美)"))
      (libsource (lib "easyedapro") (part "NCV68061SNAIT1G"))
    )
    (comp (ref "U27")
      (value "TPS5430DDAR")
      (footprint "easyedapro:ESOP-8_L4.9-W3.9-P1.27-LS6.0-TL-EP")
      (fields (field (name "Manufacturer") "TI(德州仪器)"))
      (libsource (lib "easyedapro") (part "TPS5430DDAR"))
    )
    (comp (ref "U29")
      (value "AMS1117-3.3")
      (footprint "easyedapro:SOT-223-3_L6.5-W3.4-P2.30-LS7.0-BR")
      (fields (field (name "Manufacturer") "AMS"))
      (libsource (lib "easyedapro") (part "AMS1117-3.3"))
    )
    (comp (ref "CN5")
      (value "KF250-3.5-2P-1")
      (footprint "easyedapro:CONN-TH_P3.50_KF250-3.5-2P-1")
      (fields (field (name "Manufacturer") "KEFA(科发)"))
      (libsource (lib "easyedapro") (part "KF250-3.5-2P-1"))
    )
    (comp (ref "CN6")
      (value "KF250-3.5-2P-1")
      (footprint "easyedapro:CONN-TH_P3.50_KF250-3.5-2P-1")
      (fields (field (name "Manufacturer") "KEFA(科发)"))
      (libsource (lib "easyedapro") (part "KF250-3.5-2P-1"))
    )
    (comp (ref "CN7")
      (value "KF250-3.5-2P-1")
      (footprint "easyedapro:CONN-TH_P3.50_KF250-3.5-2P-1")
      (fields (field (name "Manufacturer") "KEFA(科发)"))
      (libsource (lib "easyedapro") (part "KF250-3.5-2P-1"))
    )
    (comp (ref "D8")
      (value "1N5819WS")
      (footprint "easyedapro:SOD-323_L1.8-W1.3-LS2.5-RD")
      (fields (field (name "Manufacturer") "Hottech(合科泰)"))
      (libsource (lib "easyedapro") (part "1N5819WS"))
    )
    (comp (ref "H1")
      (value "HX PH254-01-02-Z-L11.5 male header connector")
      (footprint "easyedapro:HDR-TH_2P-P2.54-V-M_C9900056156")
      (fields (field (name "Manufacturer") "hanxia(韩下)"))
      (libsource (lib "easyedapro") (part "HX PH254-01-02-Z-L11.5 MALE HEADER CONNECTOR"))
    )
    (comp (ref "R18")
      (value "5.1kΩ")
      (footprint "easyedapro:R0402")
      (description "电阻类型:厚膜电阻;阻值:5.1kΩ;精度:±1%;功率:62.5mW;")
      (fields
        (field (name "Manufacturer Part") "0402WGF5101TCE")
        (field (name "Manufacturer") "UNI-ROYAL(厚声)")
      )
      (libsource (lib "easyedapro") (part "0402WGF5101TCE"))
    )
    (comp (ref "R19")
      (value "5.1kΩ")
      (footprint "easyedapro:R0402")
      (description "电阻类型:厚膜电阻;阻值:5.1kΩ;精度:±1%;功率:62.5mW;")
      (fields
        (field (name "Manufacturer Part") "0402WGF5101TCE")
        (field (name "Manufacturer") "UNI-ROYAL(厚声)")
      )
      (libsource (lib "easyedapro") (part "0402WGF5101TCE"))
    )
    (comp (ref "U2")
      (value "USB-TYPE-C-019")
      (footprint "easyedapro:TYPE-C-SMD_HX-TYPE-C-16PIN")
      (fields (field (name "Manufacturer") "DEALON(德艺隆)"))
      (libsource (lib "easyedapro") (part "USB-TYPE-C-019"))
    )
  )
  (nets
    (net (code "1") (name "+5V") (class "Default")
      (node (ref "C40") (pin "1") (pinfunction "1_1") (pintype "input"))
      (node (ref "C41") (pin "2") (pinfunction "2_2") (pintype "input"))
      (node (ref "C46") (pin "2") (pinfunction "2_2") (pintype "input"))
      (node (ref "C52") (pin "2") (pinfunction "2_2") (pintype "input"))
      (node (ref "C61") (pin "2") (pinfunction "2_2") (pintype "input"))
      (node (ref "D7") (pin "1") (pinfunction "K_1") (pintype "unspecified"))
      (node (ref "D8") (pin "1") (pinfunction "K_1") (pintype "unspecified"))
      (node (ref "H2") (pin "2") (pinfunction "2_2") (pintype "unspecified"))
      (node (ref "LED6") (pin "1") (pinfunction "A_1") (pintype "unspecified"))
      (node (ref "U14") (pin "3") (pinfunction "VDD_3") (pintype "input"))
      (node (ref "U29") (pin "3") (pinfunction "VIN_3") (pintype "unspecified"))
    )
    (net (code "2") (name "+12V") (class "Default")
      (node (ref "C57") (pin "2") (pinfunction "2_2") (pintype "input"))
      (node (ref "H2") (pin "1") (pinfunction "1_1") (pintype "unspecified"))
      (node (ref "LED5") (pin "1") (pinfunction "A_1") (pintype "unspecified"))
      (node (ref "Q1") (pin "1") (pinfunction "S_1") (pintype "unspecified"))
      (node (ref "Q1") (pin "2") (pinfunction "S_2") (pintype "unspecified"))
      (node (ref "Q1") (pin "3") (pinfunction "S_3") (pintype "unspecified"))
      (node (ref "U27") (pin "7") (pinfunction "VIN_7") (pintype "unspecified"))
    )
    (net (code "3") (name "3V3") (class "Default")
      (node (ref "C19") (pin "2") (pinfunction "2_2") (pintype "input"))
      (node (ref "C20") (pin "2") (pinfunction "2_2") (pintype "input"))
      (node (ref "C21") (pin "2") (pinfunction "2_2") (pintype "input"))
      (node (ref "C22") (pin "2") (pinfunction "2_2") (pintype "input"))
      (node (ref "C47") (pin "2") (pinfunction "2_2") (pintype "input"))
      (node (ref "C50") (pin "2") (pinfunction "2_2") (pintype "input"))
      (node (ref "C51") (pin "2") (pinfunction "2_2") (pintype "input"))
      (node (ref "C53") (pin "2") (pinfunction "2_2") (pintype "input"))
      (node (ref "H2") (pin "3") (pinfunction "3_3") (pintype "unspecified"))
      (node (ref "H3") (pin "3") (pinfunction "3_3") (pintype "unspecified"))
      (node (ref "L4") (pin "1") (pinfunction "1_1") (pintype "input"))
      (node (ref "R13") (pin "1") (pinfunction "1_1") (pintype "input"))
      (node (ref "R14") (pin "2") (pinfunction "2_2") (pintype "input"))
      (node (ref "R15") (pin "2") (pinfunction "2_2") (pintype "input"))
      (node (ref "U14") (pin "5") (pinfunction "VIO_5") (pintype "input"))
      (node (ref "U29") (pin "2") (pinfunction "VOUT_2") (pintype "unspecified"))
      (node (ref "U29") (pin "4") (pinfunction "VOUT_4") (pintype "unspecified"))
      (node (ref "U3") (pin "20") (pinfunction "VDD3P3_RTC_20") (pintype "input"))
      (node (ref "U3") (pin "46") (pinfunction "VDD3P3_CPU_46") (pintype "input"))
      (node (ref "U3") (pin "55") (pinfunction "VDDA_55") (pintype "input"))
      (node (ref "U3") (pin "56") (pinfunction "VDDA_56") (pintype "input"))
    )
    (net (code "4") (name "9-16V") (class "Default")
      (node (ref "C55") (pin "2") (pinfunction "2_2") (pintype "unspecified"))
      (node (ref "CN7") (pin "1") (pinfunction "1_1") (pintype "unspecified"))
      (node (ref "Q1") (pin "5") (pinfunction "D_5") (pintype "unspecified"))
      (node (ref "Q1") (pin "6") (pinfunction "D_6") (pintype "unspecified"))
      (node (ref "Q1") (pin "7") (pinfunction "D_7") (pintype "unspecified"))
      (node (ref "Q1") (pin "8") (pinfunction "D_8") (pintype "unspecified"))
      (node (ref "Q1") (pin "9") (pinfunction "D_9") (pintype "unspecified"))
      (node (ref "U26") (pin "3") (pinfunction "EN_3") (pintype "unspecified"))
      (node (ref "U26") (pin "6") (pinfunction "S_6") (pintype "unspecified"))
    )
    (net (code "5") (name "CAN_H") (class "Default")
      (node (ref "CN5") (pin "2") (pinfunction "2_2") (pintype "unspecified"))
      (node (ref "D5") (pin "2") (pinfunction "2_2") (pintype "input"))
      (node (ref "U14") (pin "7") (pinfunction "CANH_7") (pintype "input"))
    )
    (net (code "6") (name "CAN_L") (class "Default")
      (node (ref "CN5") (pin "1") (pinfunction "1_1") (pintype "unspecified"))
      (node (ref "D5") (pin "1") (pinfunction "1_1") (pintype "input"))
      (node (ref "U14") (pin "6") (pinfunction "CANL_6") (pintype "input"))
    )
    (net (code "7") (name "CHIP_PU") (class "Default")
      (node (ref "C25") (pin "2") (pinfunction "2_2") (pintype "input"))
      (node (ref "R15") (pin "1") (pinfunction "1_1") (pintype "input"))
      (node (ref "SW2") (pin "2") (pinfunction "2_2") (pintype "unspecified"))
      (node (ref "U3") (pin "4") (pinfunction "CHIP_PU_4") (pintype "input"))
    )
    (net (code "8") (name "GND") (class "Default")
      (node (ref "C19") (pin "1") (pinfunction "1_1") (pintype "input"))
      (node (ref "C20") (pin "1") (pinfunction "1_1") (pintype "input"))
      (node (ref "C21") (pin "1") (pinfunction "1_1") (pintype "input"))
      (node (ref "C22") (pin "1") (pinfunction "1_1") (pintype "input"))
      (node (ref "C23") (pin "1") (pinfunction "1_1") (pintype "input"))
      (node (ref "C25") (pin "1") (pinfunction "1_1") (pintype "input"))
      (node (ref "C33") (pin "1") (pinfunction "1_1") (pintype "input"))
      (node (ref "C34") (pin "2") (pinfunction "2_2") (pintype "input"))
      (node (ref "C40") (pin "2") (pinfunction "2_2") (pintype "input"))
      (node (ref "C41") (pin "1") (pinfunction "1_1") (pintype "input"))
      (node (ref "C46") (pin "1") (pinfunction "1_1") (pintype "input"))
      (node (ref "C47") (pin "1") (pinfunction "1_1") (pintype "input"))
      (node (ref "C50") (pin "1") (pinfunction "1_1") (pintype "input"))
      (node (ref "C51") (pin "1") (pinfunction "1_1") (pintype "input"))
      (node (ref "C52") (pin "1") (pinfunction "1_1") (pintype "input"))
      (node (ref "C53") (pin "1") (pinfunction "1_1") (pintype "input"))
      (node (ref "C55") (pin "1") (pinfunction "1_1") (pintype "unspecified"))
      (node (ref "C57") (pin "1") (pinfunction "1_1") (pintype "input"))
      (node (ref "C59") (pin "1") (pinfunction "1_1") (pintype "input"))
      (node (ref "C60") (pin "1") (pinfunction "1_1") (pintype "input"))
      (node (ref "C61") (pin "1") (pinfunction "1_1") (pintype "input"))
      (node (ref "CN7") (pin "2") (pinfunction "2_2") (pintype "unspecified"))
      (node (ref "D5") (pin "3") (pinfunction "3_3") (pintype "input"))
      (node (ref "D6") (pin "1") (pinfunction "A_1") (pintype "unspecified"))
      (node (ref "H1") (pin "2") (pinfunction "2_2") (pintype "unspecified"))
      (node (ref "H2") (pin "4") (pinfunction "4_4") (pintype "unspecified"))
      (node (ref "H3") (pin "4") (pinfunction "4_4") (pintype "unspecified"))
      (node (ref "L6") (pin "2") (pinfunction "2_2") (pintype "input"))
      (node (ref "L7") (pin "2") (pinfunction "2_2") (pintype "unspecified"))
      (node (ref "LED7") (pin "2") (pinfunction "K_2") (pintype "unspecified"))
      (node (ref "R18") (pin "1") (pinfunction "1_1") (pintype "input"))
      (node (ref "R19") (pin "1") (pinfunction "1_1") (pintype "input"))
      (node (ref "R26") (pin "2") (pinfunction "2_2") (pintype "input"))
      (node (ref "R28") (pin "1") (pinfunction "1_1") (pintype "input"))
      (node (ref "R29") (pin "2") (pinfunction "2_2") (pintype "input"))
      (node (ref "R31") (pin "2") (pinfunction "2_2") (pintype "input"))
      (node (ref "SW1") (pin "1") (pinfunction "1_1") (pintype "unspecified"))
      (node (ref "SW2") (pin "1") (pinfunction "1_1") (pintype "unspecified"))
      (node (ref "U14") (pin "2") (pinfunction "VSS_2") (pintype "input"))
      (node (ref "U14") (pin "8") (pinfunction "STBY_8") (pintype "input"))
      (node (ref "U2") (pin "1") (pinfunction "1_1") (pintype "input"))
      (node (ref "U2") (pin "A1") (pinfunction "A1_A1") (pintype "input"))
      (node (ref "U2") (pin "A12") (pinfunction "A12_A12") (pintype "input"))
      (node (ref "U26") (pin "2") (pinfunction "GND_2") (pintype "unspecified"))
      (node (ref "U26") (pin "4") (pinfunction "D_4") (pintype "unspecified"))
      (node (ref "U27") (pin "6") (pinfunction "GND_6") (pintype "unspecified"))
      (node (ref "U27") (pin "9") (pinfunction "PowerPAD_9") (pintype "unspecified"))
      (node (ref "U28") (pin "2") (pinfunction "Cathode_2") (pintype "unspecified"))
      (node (ref "U29") (pin "1") (pinfunction "GND_1") (pintype "unspecified"))
      (node (ref "U3") (pin "57") (pinfunction "GND_57") (pintype "input"))
      (node (ref "U5") (pin "4") (pinfunction "VSS_4") (pintype "input"))
      (node (ref "X1") (pin "2") (pinfunction "GND_2") (pintype "input"))
      (node (ref "X1") (pin "4") (pinfunction "GND_4") (pintype "input"))
    )
    (net (code "9") (name "GPIO0") (class "Default")
      (node (ref "R14") (pin "1") (pinfunction "1_1") (pintype "input"))
      (node (ref "SW1") (pin "2") (pinfunction "2_2") (pintype "unspecified"))
      (node (ref "U3") (pin "5") (pinfunction "GPIO0_5") (pintype "input"))
    )
    (net (code "10") (name "GPIO1") (class "Default")
      (node (ref "U3") (pin "6") (pinfunction "GPIO1_6") (pintype "input"))
    )
    (net (code "11") (name "GPIO2") (class "Default")
      (node (ref "U3") (pin "7") (pinfunction "GPIO2_7") (pintype "input"))
    )
    (net (code "12") (name "GPIO3") (class "Default")
      (node (ref "U3") (pin "8") (pinfunction "GPIO3_8") (pintype "input"))
    )
    (net (code "13") (name "GPIO4") (class "Default")
      (node (ref "U3") (pin "9") (pinfunction "GPIO4_9") (pintype "input"))
    )
    (net (code "14") (name "GPIO5") (class "Default")
      (node (ref "U3") (pin "10") (pinfunction "GPIO5_10") (pintype "input"))
    )
    (net (code "15") (name "GPIO6") (class "Default")
      (node (ref "U3") (pin "11") (pinfunction "GPIO6_11") (pintype "input"))
    )
    (net (code "16") (name "GPIO7") (class "Default")
      (node (ref "U3") (pin "12") (pinfunction "GPIO7_12") (pintype "input"))
    )
    (net (code "17") (name "GPIO8") (class "Default")
      (node (ref "U3") (pin "13") (pinfunction "GPIO8_13") (pintype "input"))
    )
    (net (code "18") (name "GPIO9") (class "Default")
      (node (ref "U3") (pin "14") (pinfunction "GPIO9_14") (pintype "input"))
    )
    (net (code "19") (name "GPIO10") (class "Default")
      (node (ref "U14") (pin "1") (pinfunction "TXD_1") (pintype "input"))
      (node (ref "U3") (pin "15") (pinfunction "GPIO10_15") (pintype "input"))
    )
    (net (code "20") (name "GPIO11") (class "Default")
      (node (ref "U14") (pin "4") (pinfunction "RXD_4") (pintype "input"))
      (node (ref "U3") (pin "16") (pinfunction "GPIO11_16") (pintype "input"))
    )
    (net (code "21") (name "GPIO12") (class "Default")
      (node (ref "U3") (pin "17") (pinfunction "GPIO12_17") (pintype "input"))
    )
    (net (code "22") (name "GPIO13") (class "Default")
      (node (ref "U3") (pin "18") (pinfunction "GPIO13_18") (pintype "input"))
    )
    (net (code "23") (name "GPIO14") (class "Default")
      (node (ref "U3") (pin "19") (pinfunction "GPIO14_19") (pintype "input"))
    )
    (net (code "24") (name "GPIO15") (class "Default")
      (node (ref "U3") (pin "21") (pinfunction "XTAL_32K_P_21") (pintype "input"))
    )
    (net (code "25") (name "GPIO16") (class "Default")
      (node (ref "U3") (pin "22") (pinfunction "XTAL_32K_N_22") (pintype "input"))
    )
    (net (code "26") (name "GPIO17") (class "Default")
      (node (ref "U3") (pin "23") (pinfunction "GPIO17_23") (pintype "input"))
    )
    (net (code "27") (name "GPIO18") (class "Default")
      (node (ref "LED8") (pin "1") (pinfunction "A_1") (pintype "unspecified"))
      (node (ref "R32") (pin "1") (pinfunction "1_1") (pintype "input"))
      (node (ref "U3") (pin "24") (pinfunction "GPIO18_24") (pintype "input"))
    )
    (net (code "28") (name "GPIO21") (class "Default")
      (node (ref "U3") (pin "27") (pinfunction "GPIO21_27") (pintype "input"))
    )
    (net (code "29") (name "GPIO33") (class "Default")
      (node (ref "U3") (pin "38") (pinfunction "GPIO33_38") (pintype "input"))
    )
    (net (code "30") (name "GPIO34") (class "Default")
      (node (ref "U3") (pin "39") (pinfunction "GPIO34_39") (pintype "input"))
    )
    (net (code "31") (name "GPIO35") (class "Default")
      (node (ref "U3") (pin "40") (pinfunction "GPIO35_40") (pintype "input"))
    )
    (net (code "32") (name "GPIO36") (class "Default")
      (node (ref "U3") (pin "41") (pinfunction "GPIO36_41") (pintype "input"))
    )
    (net (code "33") (name "GPIO37") (class "Default")
      (node (ref "U3") (pin "42") (pinfunction "GPIO37_42") (pintype "input"))
    )
    (net (code "34") (name "GPIO38") (class "Default")
      (node (ref "U3") (pin "43") (pinfunction "GPIO38_43") (pintype "input"))
    )
    (net (code "35") (name "GPIO39") (class "Default")
      (node (ref "U3") (pin "44") (pinfunction "MTCK_44") (pintype "input"))
    )
    (net (code "36") (name "GPIO40") (class "Default")
      (node (ref "U3") (pin "45") (pinfunction "MTDO_45") (pintype "input"))
    )
    (net (code "37") (name "GPIO41") (class "Default")
      (node (ref "U3") (pin "47") (pinfunction "MTDI_47") (pintype "input"))
    )
    (net (code "38") (name "GPIO42") (class "Default")
      (node (ref "U3") (pin "48") (pinfunction "MTMS_48") (pintype "input"))
    )
    (net (code "39") (name "GPIO45") (class "Default")
      (node (ref "U3") (pin "51") (pinfunction "GPIO45_51") (pintype "input"))
    )
    (net (code "40") (name "GPIO46") (class "Default")
      (node (ref "U3") (pin "52") (pinfunction "GPIO46_52") (pintype "input"))
    )
    (net (code "41") (name "GPIO47") (class "Default")
      (node (ref "U3") (pin "37") (pinfunction "SPICLK_P_37") (pintype "input"))
    )
    (net (code "42") (name "GPIO48") (class "Default")
      (node (ref "U3") (pin "36") (pinfunction "SPICLK_N_36") (pintype "input"))
    )
    (net (code "43") (name "Net-(C54-Pad1)") (class "Default")
      (node (ref "C54") (pin "1") (pinfunction "1_1") (pintype "input"))
      (node (ref "L7") (pin "1") (pinfunction "1_1") (pintype "unspecified"))
      (node (ref "U25") (pin "2") (pinfunction "2_2") (pintype "input"))
    )
    (net (code "44") (name "Net-(D6-K)") (class "Default")
      (node (ref "C58") (pin "2") (pinfunction "2_2") (pintype "unspecified"))
      (node (ref "D6") (pin "2") (pinfunction "K_2") (pintype "unspecified"))
      (node (ref "L9") (pin "1") (pinfunction "1_1") (pintype "unspecified"))
      (node (ref "U27") (pin "8") (pinfunction "PH_8") (pintype "unspecified"))
    )
    (net (code "45") (name "Net-(D7-A)") (class "Default")
      (node (ref "C59") (pin "2") (pinfunction "2_2") (pintype "input"))
      (node (ref "C60") (pin "2") (pinfunction "2_2") (pintype "input"))
      (node (ref "D7") (pin "2") (pinfunction "A_2") (pintype "unspecified"))
      (node (ref "L9") (pin "2") (pinfunction "2_2") (pintype "unspecified"))
      (node (ref "R27") (pin "2") (pinfunction "2_2") (pintype "input"))
    )
    (net (code "46") (name "Net-(L4-Pad2)") (class "Default")
      (node (ref "L4") (pin "2") (pinfunction "2_2") (pintype "input"))
      (node (ref "U3") (pin "2") (pinfunction "VDD3P3_2") (pintype "input"))
      (node (ref "U3") (pin "3") (pinfunction "VDD3P3_3") (pintype "input"))
    )
    (net (code "47") (name "Net-(LED5-K)") (class "Default")
      (node (ref "LED5") (pin "2") (pinfunction "K_2") (pintype "unspecified"))
      (node (ref "R26") (pin "1") (pinfunction "1_1") (pintype "input"))
    )
    (net (code "48") (name "Net-(LED6-K)") (class "Default")
      (node (ref "LED6") (pin "2") (pinfunction "K_2") (pintype "unspecified"))
      (node (ref "R29") (pin "1") (pinfunction "1_1") (pintype "input"))
    )
    (net (code "49") (name "Net-(LED7-A)") (class "Default")
      (node (ref "LED7") (pin "1") (pinfunction "A_1") (pintype "unspecified"))
      (node (ref "R13") (pin "2") (pinfunction "2_2") (pintype "input"))
    )
    (net (code "50") (name "Net-(LED8-K)") (class "Default")
      (node (ref "LED8") (pin "2") (pinfunction "K_2") (pintype "unspecified"))
      (node (ref "R31") (pin "1") (pinfunction "1_1") (pintype "input"))
    )
    (net (code "51") (name "Net-(Q1-G)") (class "Default")
      (node (ref "Q1") (pin "4") (pinfunction "G_4") (pintype "unspecified"))
      (node (ref "U26") (pin "5") (pinfunction "G_5") (pintype "unspecified"))
    )
    (net (code "52") (name "Net-(R18-Pad2)") (class "Default")
      (node (ref "R18") (pin "2") (pinfunction "2_2") (pintype "input"))
      (node (ref "U2") (pin "A5") (pinfunction "A5_A5") (pintype "input"))
    )
    (net (code "53") (name "Net-(R19-Pad2)") (class "Default")
      (node (ref "R19") (pin "2") (pinfunction "2_2") (pintype "input"))
      (node (ref "U2") (pin "B5") (pinfunction "B5_B5") (pintype "input"))
    )
    (net (code "54") (name "Net-(U3-LNA_IN)") (class "Default")
      (node (ref "C54") (pin "2") (pinfunction "2_2") (pintype "input"))
      (node (ref "L6") (pin "1") (pinfunction "1_1") (pintype "input"))
      (node (ref "U3") (pin "1") (pinfunction "LNA_IN_1") (pintype "input"))
    )
    (net (code "55") (name "Net-(U3-XTAL_P)") (class "Default")
      (node (ref "L8") (pin "1") (pinfunction "1_1") (pintype "input"))
      (node (ref "U3") (pin "54") (pinfunction "XTAL_P_54") (pintype "input"))
    )
    (net (code "56") (name "Net-(U27-BOOT)") (class "Default")
      (node (ref "C58") (pin "1") (pinfunction "1_1") (pintype "unspecified"))
      (node (ref "U27") (pin "1") (pinfunction "BOOT_1") (pintype "unspecified"))
    )
    (net (code "57") (name "Net-(U27-VSENSE)") (class "Default")
      (node (ref "R27") (pin "1") (pinfunction "1_1") (pintype "input"))
      (node (ref "R28") (pin "2") (pinfunction "2_2") (pintype "input"))
      (node (ref "U27") (pin "4") (pinfunction "VSENSE_4") (pintype "unspecified"))
    )
    (net (code "58") (name "Net-(U28-Anode)") (class "Default")
      (node (ref "R32") (pin "2") (pinfunction "2_2") (pintype "input"))
      (node (ref "U28") (pin "1") (pinfunction "Anode_1") (pintype "unspecified"))
    )
    (net (code "59") (name "SPICLK") (class "Default")
      (node (ref "U3") (pin "33") (pinfunction "SPICLK_33") (pintype "input"))
      (node (ref "U5") (pin "6") (pinfunction "SCLK_6") (pintype "input"))
    )
    (net (code "60") (name "SPICS0") (class "Default")
      (node (ref "U3") (pin "32") (pinfunction "SPICS0_32") (pintype "input"))
      (node (ref "U5") (pin "1") (pinfunction "/CS_1") (pintype "input"))
    )
    (net (code "61") (name "SPICS1") (class "Default")
      (node (ref "U3") (pin "28") (pinfunction "SPICS1_28") (pintype "input"))
    )
    (net (code "62") (name "SPID") (class "Default")
      (node (ref "U3") (pin "35") (pinfunction "SPID_35") (pintype "input"))
      (node (ref "U5") (pin "5") (pinfunction "SI_5") (pintype "input"))
    )
    (net (code "63") (name "SPIHD") (class "Default")
      (node (ref "U3") (pin "30") (pinfunction "SPIHD_30") (pintype "input"))
      (node (ref "U5") (pin "7") (pinfunction "/HOLD_7") (pintype "input"))
    )
    (net (code "64") (name "SPIQ") (class "Default")
      (node (ref "U3") (pin "34") (pinfunction "SPIQ_34") (pintype "input"))
      (node (ref "U5") (pin "2") (pinfunction "SO_2") (pintype "input"))
    )
    (net (code "65") (name "SPIWP") (class "Default")
      (node (ref "U3") (pin "31") (pinfunction "SPIWP_31") (pintype "input"))
      (node (ref "U5") (pin "3") (pinfunction "/WP_3") (pintype "input"))
    )
    (net (code "66") (name "SWITCH") (class "Default")
      (node (ref "CN6") (pin "1") (pinfunction "1_1") (pintype "unspecified"))
      (node (ref "U28") (pin "4") (pinfunction "Collector_4") (pintype "unspecified"))
    )
    (net (code "67") (name "SWITCH_GND") (class "Default")
      (node (ref "CN6") (pin "2") (pinfunction "2_2") (pintype "unspecified"))
      (node (ref "H1") (pin "1") (pinfunction "1_1") (pintype "unspecified"))
      (node (ref "U28") (pin "3") (pinfunction "Emitter_3") (pintype "unspecified"))
    )
    (net (code "68") (name "U0RX") (class "Default")
      (node (ref "H3") (pin "1") (pinfunction "1_1") (pintype "unspecified"))
      (node (ref "U3") (pin "50") (pinfunction "U0RXD_50") (pintype "input"))
    )
    (net (code "69") (name "U0TX") (class "Default")
      (node (ref "H3") (pin "2") (pinfunction "2_2") (pintype "unspecified"))
      (node (ref "U3") (pin "49") (pinfunction "U0TXD_49") (pintype "input"))
    )
    (net (code "70") (name "USB_D+") (class "Default")
      (node (ref "U2") (pin "A6") (pinfunction "A6_A6") (pintype "input"))
      (node (ref "U2") (pin "B6") (pinfunction "B6_B6") (pintype "input"))
      (node (ref "U3") (pin "26") (pinfunction "GPIO20_26") (pintype "input"))
    )
    (net (code "71") (name "USB_D-") (class "Default")
      (node (ref "U2") (pin "A7") (pinfunction "A7_A7") (pintype "input"))
      (node (ref "U2") (pin "B7") (pinfunction "B7_B7") (pintype "input"))
      (node (ref "U3") (pin "25") (pinfunction "GPIO19_25") (pintype "input"))
    )
    (net (code "72") (name "VDD_SPI") (class "Default")
      (node (ref "C23") (pin "2") (pinfunction "2_2") (pintype "input"))
      (node (ref "U3") (pin "29") (pinfunction "VDD_SPI_29") (pintype "input"))
      (node (ref "U5") (pin "8") (pinfunction "VCC_8") (pintype "input"))
    )
    (net (code "73") (name "VUSB") (class "Default")
      (node (ref "D8") (pin "2") (pinfunction "A_2") (pintype "unspecified"))
      (node (ref "U2") (pin "A4") (pinfunction "A4_A4") (pintype "input"))
      (node (ref "U2") (pin "A9") (pinfunction "A9_A9") (pintype "input"))
    )
    (net (code "74") (name "XTAL_N") (class "Default")
      (node (ref "C34") (pin "1") (pinfunction "1_1") (pintype "input"))
      (node (ref "U3") (pin "53") (pinfunction "XTAL_N_53") (pintype "input"))
      (node (ref "X1") (pin "3") (pinfunction "3_3") (pintype "input"))
    )
    (net (code "75") (name "XTAL_P") (class "Default")
      (node (ref "C33") (pin "2") (pinfunction "2_2") (pintype "input"))
      (node (ref "L8") (pin "2") (pinfunction "2_2") (pintype "input"))
      (node (ref "X1") (pin "1") (pinfunction "1_1") (pintype "input"))
    )
    (net (code "76") (name "unconnected-(U2-PadA8)") (class "Default")
      (node (ref "U2") (pin "A8") (pinfunction "A8_A8") (pintype "input+no_connect"))
    )
    (net (code "77") (name "unconnected-(U2-PadB8)") (class "Default")
      (node (ref "U2") (pin "B8") (pinfunction "B8_B8") (pintype "input+no_connect"))
    )
    (net (code "78") (name "unconnected-(U25-Pad1)") (class "Default")
      (node (ref "U25") (pin "1") (pinfunction "1_1") (pintype "input+no_connect"))
    )
    (net (code "79") (name "unconnected-(U26-NC-Pad1)") (class "Default")
      (node (ref "U26") (pin "1") (pinfunction "NC_1") (pintype "unspecified+no_connect"))
    )
    (net (code "80") (name "unconnected-(U27-ENA-Pad5)") (class "Default")
      (node (ref "U27") (pin "5") (pinfunction "ENA_5") (pintype "unspecified+no_connect"))
    )
    (net (code "81") (name "unconnected-(U27-NC-Pad2)") (class "Default")
      (node (ref "U27") (pin "2") (pinfunction "NC_2") (pintype "unspecified+no_connect"))
    )
    (net (code "82") (name "unconnected-(U27-NC-Pad3)") (class "Default")
      (node (ref "U27") (pin "3") (pinfunction "NC_3") (pintype "unspecified+no_connect"))
    )
  )
)
